# AVT5805_SCH_DF.net
KiCad netlist of a schematic drawn in Altium Designer
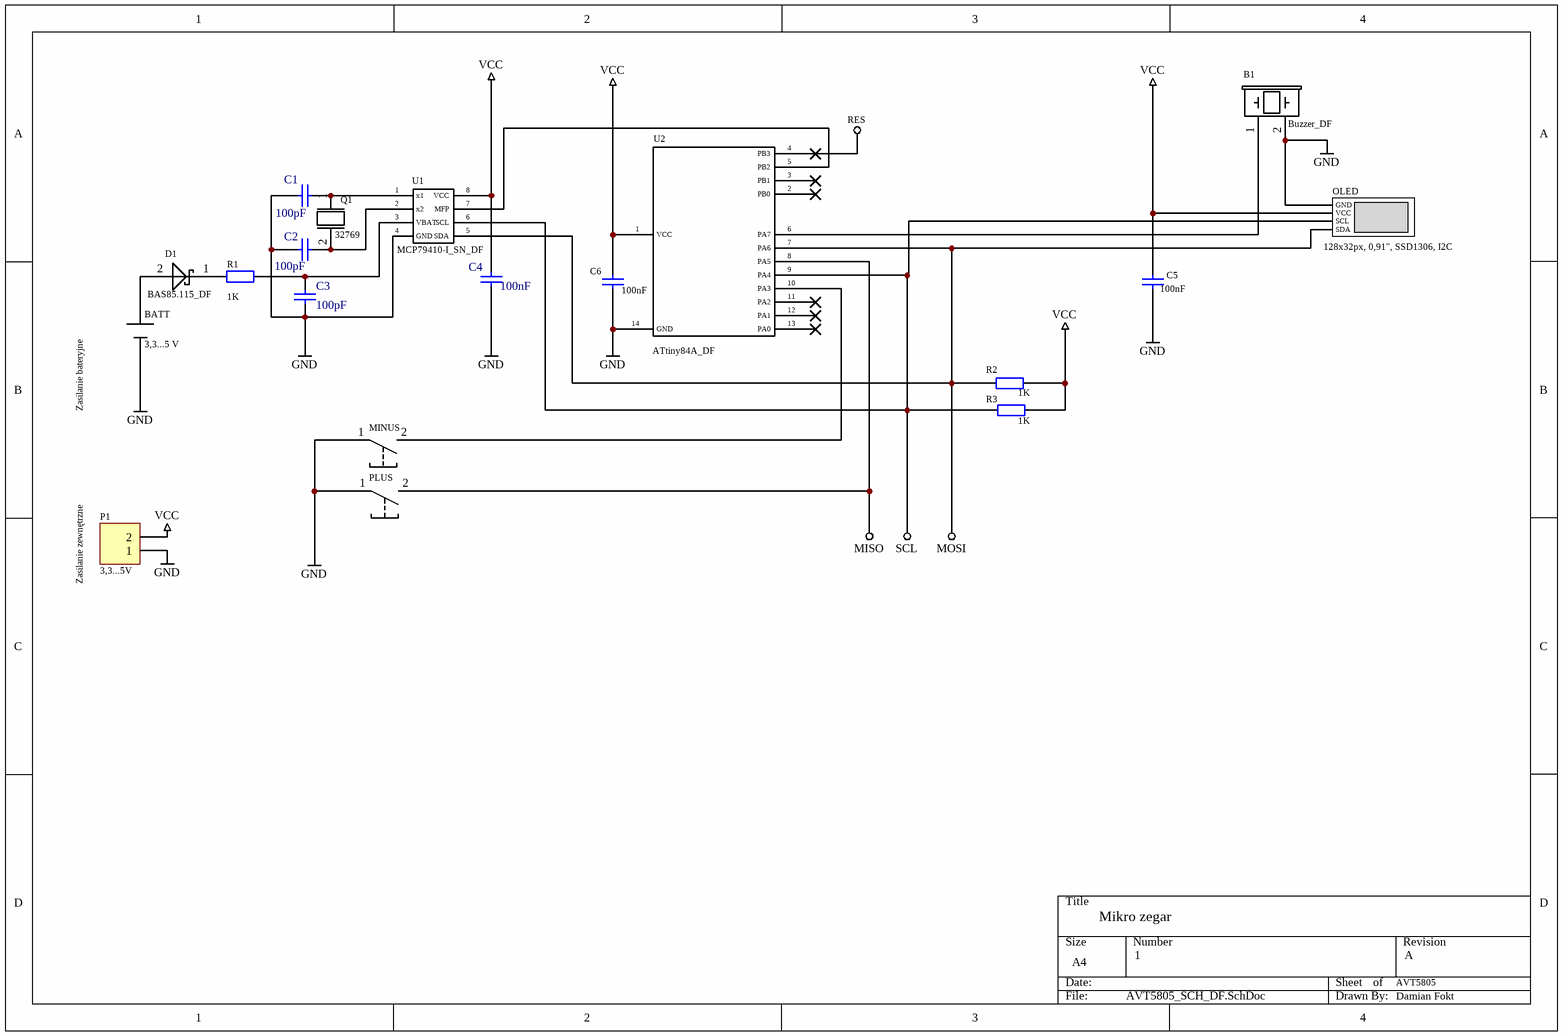
[diagram p0: AVT5805_SCH_DF.SchDoc]

(export (version "E")
  (design (tool "Eeschema 10.0.6"))
  (components
    (comp (ref "32769")
      (value "Q1")
      (footprint "DT-38")
      (libsource (lib "AVT5805_DF") (part "Quartz_resonator_DF"))
    )
    (comp (ref "B1")
      (value "Buzzer_DF")
      (footprint "LPT9018BS")
      (libsource (lib "AVT5805_DF") (part "Buzzer_DF"))
    )
    (comp (ref "BATT")
      (value "3,3...5 V")
      (footprint "DS1092")
      (libsource (lib "AVT5805_DF") (part "Battery_Socket_DF"))
    )
    (comp (ref "C1")
      (value "100pF")
      (footprint "C1206")
      (description "Capacitor (Semiconductor SIM Model)")
      (fields (field (name "Comment") "Cap Semi") (field (name "PUBLISHER") "Altium Limited"))
      (libsource (lib "Miscellaneous Devices") (part "Cap Semi"))
    )
    (comp (ref "C2")
      (value "100pF")
      (footprint "C1206")
      (description "Capacitor (Semiconductor SIM Model)")
      (fields (field (name "Comment") "Cap Semi") (field (name "PUBLISHER") "Altium Limited"))
      (libsource (lib "Miscellaneous Devices") (part "Cap Semi"))
    )
    (comp (ref "C3")
      (value "100pF")
      (footprint "C1206")
      (description "Capacitor (Semiconductor SIM Model)")
      (fields (field (name "Comment") "Cap Semi") (field (name "PUBLISHER") "Altium Limited"))
      (libsource (lib "Miscellaneous Devices") (part "Cap Semi"))
    )
    (comp (ref "C4")
      (value "100nF")
      (footprint "C1206")
      (description "Capacitor (Semiconductor SIM Model)")
      (fields (field (name "Comment") "Cap Semi") (field (name "PUBLISHER") "Altium Limited"))
      (libsource (lib "Miscellaneous Devices") (part "Cap Semi"))
    )
    (comp (ref "C5")
      (value "100nF")
      (footprint "C1206")
      (description "Capacitor (Semiconductor SIM Model)")
      (fields (field (name "Comment") "Cap Semi") (field (name "PUBLISHER") "Altium Limited"))
      (libsource (lib "Miscellaneous Devices") (part "Cap Semi"))
    )
    (comp (ref "C6")
      (value "100nF")
      (footprint "C1206")
      (description "Capacitor (Semiconductor SIM Model)")
      (fields (field (name "Comment") "Cap Semi") (field (name "PUBLISHER") "Altium Limited"))
      (libsource (lib "Miscellaneous Devices") (part "Cap Semi"))
    )
    (comp (ref "D1")
      (value "BAS85.115_DF")
      (footprint "MINIMELF")
      (libsource (lib "AVT5805_DF") (part "BAS85.115_DF"))
    )
    (comp (ref "MINUS")
      (value "Button_DF")
      (footprint "DTSM31NB")
      (libsource (lib "AVT5805_DF") (part "Button_DF"))
    )
    (comp (ref "OLED")
      (value "128x32px, 0,91\", SSD1306, I2C")
      (footprint "SSD1306")
      (libsource (lib "AVT5805_DF") (part "OLED_Screen_DF"))
    )
    (comp (ref "P1")
      (value "3,3...5V")
      (footprint "HDR1X2")
      (description "Header, 2-Pin")
      (fields (field (name "PUBLISHER") "Altium Limited"))
      (libsource (lib "Miscellaneous Connectors") (part "Header 2"))
    )
    (comp (ref "PLUS")
      (value "Button_DF")
      (footprint "DTSM31NB")
      (libsource (lib "AVT5805_DF") (part "Button_DF"))
    )
    (comp (ref "R1")
      (value "1K")
      (footprint "RESC6332")
      (description "Resistor")
      (fields (field (name "Comment") "Res2") (field (name "PUBLISHER") "Altium Limited"))
      (libsource (lib "Miscellaneous Devices") (part "Res2"))
    )
    (comp (ref "R2")
      (value "1K")
      (footprint "RESC6332")
      (description "Resistor")
      (fields (field (name "Comment") "Res2") (field (name "PUBLISHER") "Altium Limited"))
      (libsource (lib "Miscellaneous Devices") (part "Res2"))
    )
    (comp (ref "R3")
      (value "1K")
      (footprint "RESC6332")
      (description "Resistor")
      (fields (field (name "Comment") "Res2") (field (name "PUBLISHER") "Altium Limited"))
      (libsource (lib "Miscellaneous Devices") (part "Res2"))
    )
    (comp (ref "U1")
      (value "MCP79410-I_SN_DF")
      (footprint "SO08")
      (libsource (lib "AVT5805_DF") (part "MCP79410-I_SN_DF"))
    )
    (comp (ref "U2")
      (value "ATtiny84A_DF")
      (footprint "SOIC14")
      (libsource (lib "AVT5805_DF") (part "ATtiny84A_DF"))
    )
  )
  (nets
    (net (code "1") (name "GND") (class "Default")
      (node (ref "B1") (pin "2") (pinfunction "2_2") (pintype "passive"))
      (node (ref "BATT") (pin "2") (pinfunction "GND_2") (pintype "passive"))
      (node (ref "C1") (pin "1") (pinfunction "1_1") (pintype "passive"))
      (node (ref "C2") (pin "1") (pinfunction "1_1") (pintype "passive"))
      (node (ref "C3") (pin "1") (pinfunction "1_1") (pintype "passive"))
      (node (ref "C4") (pin "1") (pinfunction "1_1") (pintype "passive"))
      (node (ref "C5") (pin "1") (pinfunction "1_1") (pintype "passive"))
      (node (ref "C6") (pin "1") (pinfunction "1_1") (pintype "passive"))
      (node (ref "MINUS") (pin "1") (pinfunction "1_1") (pintype "passive"))
      (node (ref "OLED") (pin "1") (pinfunction "GND_1") (pintype "passive"))
      (node (ref "P1") (pin "1") (pinfunction "1_1") (pintype "passive"))
      (node (ref "PLUS") (pin "1") (pinfunction "1_1") (pintype "passive"))
      (node (ref "U1") (pin "4") (pinfunction "GND_4") (pintype "passive"))
      (node (ref "U2") (pin "14") (pinfunction "GND_14") (pintype "passive"))
    )
    (net (code "2") (name "MISO") (class "Default")
      (node (ref "PLUS") (pin "2") (pinfunction "2_2") (pintype "passive"))
      (node (ref "U2") (pin "8") (pinfunction "PA5_8") (pintype "passive"))
    )
    (net (code "3") (name "MOSI") (class "Default")
      (node (ref "OLED") (pin "3") (pinfunction "SDA_3") (pintype "passive"))
      (node (ref "R2") (pin "1") (pinfunction "1_1") (pintype "passive"))
      (node (ref "U1") (pin "5") (pinfunction "SDA_5") (pintype "passive"))
      (node (ref "U2") (pin "7") (pinfunction "PA6_7") (pintype "passive"))
    )
    (net (code "4") (name "Net-(BATT-VCC)") (class "Default")
      (node (ref "BATT") (pin "1") (pinfunction "VCC_1") (pintype "passive"))
      (node (ref "D1") (pin "2") (pintype "passive"))
    )
    (net (code "5") (name "Net-(D1-Pad1)") (class "Default")
      (node (ref "D1") (pin "1") (pintype "passive"))
      (node (ref "R1") (pin "1") (pinfunction "1_1") (pintype "passive"))
    )
    (net (code "6") (name "Net-(U1-MFP)") (class "Default")
      (node (ref "U1") (pin "7") (pinfunction "MFP_7") (pintype "passive"))
      (node (ref "U2") (pin "5") (pinfunction "PB2_5") (pintype "passive"))
    )
    (net (code "7") (name "Net-(U1-VBAT)") (class "Default")
      (node (ref "C3") (pin "2") (pinfunction "2_2") (pintype "passive"))
      (node (ref "R1") (pin "2") (pinfunction "2_2") (pintype "passive"))
      (node (ref "U1") (pin "3") (pinfunction "VBAT_3") (pintype "passive"))
    )
    (net (code "8") (name "Net-(U1-x1)") (class "Default")
      (node (ref "32769") (pin "1") (pintype "passive"))
      (node (ref "C1") (pin "2") (pinfunction "2_2") (pintype "passive"))
      (node (ref "U1") (pin "1") (pinfunction "x1_1") (pintype "passive"))
    )
    (net (code "9") (name "Net-(U1-x2)") (class "Default")
      (node (ref "32769") (pin "2") (pintype "passive"))
      (node (ref "C2") (pin "2") (pinfunction "2_2") (pintype "passive"))
      (node (ref "U1") (pin "2") (pinfunction "x2_2") (pintype "passive"))
    )
    (net (code "10") (name "Net-(U2-PA3)") (class "Default")
      (node (ref "MINUS") (pin "2") (pinfunction "2_2") (pintype "passive"))
      (node (ref "U2") (pin "10") (pinfunction "PA3_10") (pintype "passive"))
    )
    (net (code "11") (name "Net-(U2-PA7)") (class "Default")
      (node (ref "B1") (pin "1") (pinfunction "1_1") (pintype "passive"))
      (node (ref "U2") (pin "6") (pinfunction "PA7_6") (pintype "passive"))
    )
    (net (code "12") (name "RES") (class "Default")
      (node (ref "U2") (pin "4") (pinfunction "PB3_4") (pintype "passive"))
    )
    (net (code "13") (name "SCL") (class "Default")
      (node (ref "OLED") (pin "4") (pinfunction "SCL_4") (pintype "passive"))
      (node (ref "R3") (pin "1") (pinfunction "1_1") (pintype "passive"))
      (node (ref "U1") (pin "6") (pinfunction "SCL_6") (pintype "passive"))
      (node (ref "U2") (pin "9") (pinfunction "PA4_9") (pintype "passive"))
    )
    (net (code "14") (name "VCC") (class "Default")
      (node (ref "C4") (pin "2") (pinfunction "2_2") (pintype "passive"))
      (node (ref "C5") (pin "2") (pinfunction "2_2") (pintype "passive"))
      (node (ref "C6") (pin "2") (pinfunction "2_2") (pintype "passive"))
      (node (ref "OLED") (pin "2") (pinfunction "VCC_2") (pintype "passive"))
      (node (ref "P1") (pin "2") (pinfunction "2_2") (pintype "passive"))
      (node (ref "R2") (pin "2") (pinfunction "2_2") (pintype "passive"))
      (node (ref "R3") (pin "2") (pinfunction "2_2") (pintype "passive"))
      (node (ref "U1") (pin "8") (pinfunction "VCC_8") (pintype "passive"))
      (node (ref "U2") (pin "1") (pinfunction "VCC_1") (pintype "passive"))
    )
    (net (code "15") (name "unconnected-(U2-PA0-Pad13)") (class "Default")
      (node (ref "U2") (pin "13") (pinfunction "PA0_13") (pintype "passive+no_connect"))
    )
    (net (code "16") (name "unconnected-(U2-PA1-Pad12)") (class "Default")
      (node (ref "U2") (pin "12") (pinfunction "PA1_12") (pintype "passive+no_connect"))
    )
    (net (code "17") (name "unconnected-(U2-PA2-Pad11)") (class "Default")
      (node (ref "U2") (pin "11") (pinfunction "PA2_11") (pintype "passive+no_connect"))
    )
    (net (code "18") (name "unconnected-(U2-PB0-Pad2)") (class "Default")
      (node (ref "U2") (pin "2") (pinfunction "PB0_2") (pintype "passive+no_connect"))
    )
    (net (code "19") (name "unconnected-(U2-PB1-Pad3)") (class "Default")
      (node (ref "U2") (pin "3") (pinfunction "PB1_3") (pintype "passive+no_connect"))
    )
  )
)
